# Arduino-Pro-v16_Silk_1.net
KiCad netlist of a schematic drawn in EAGLE
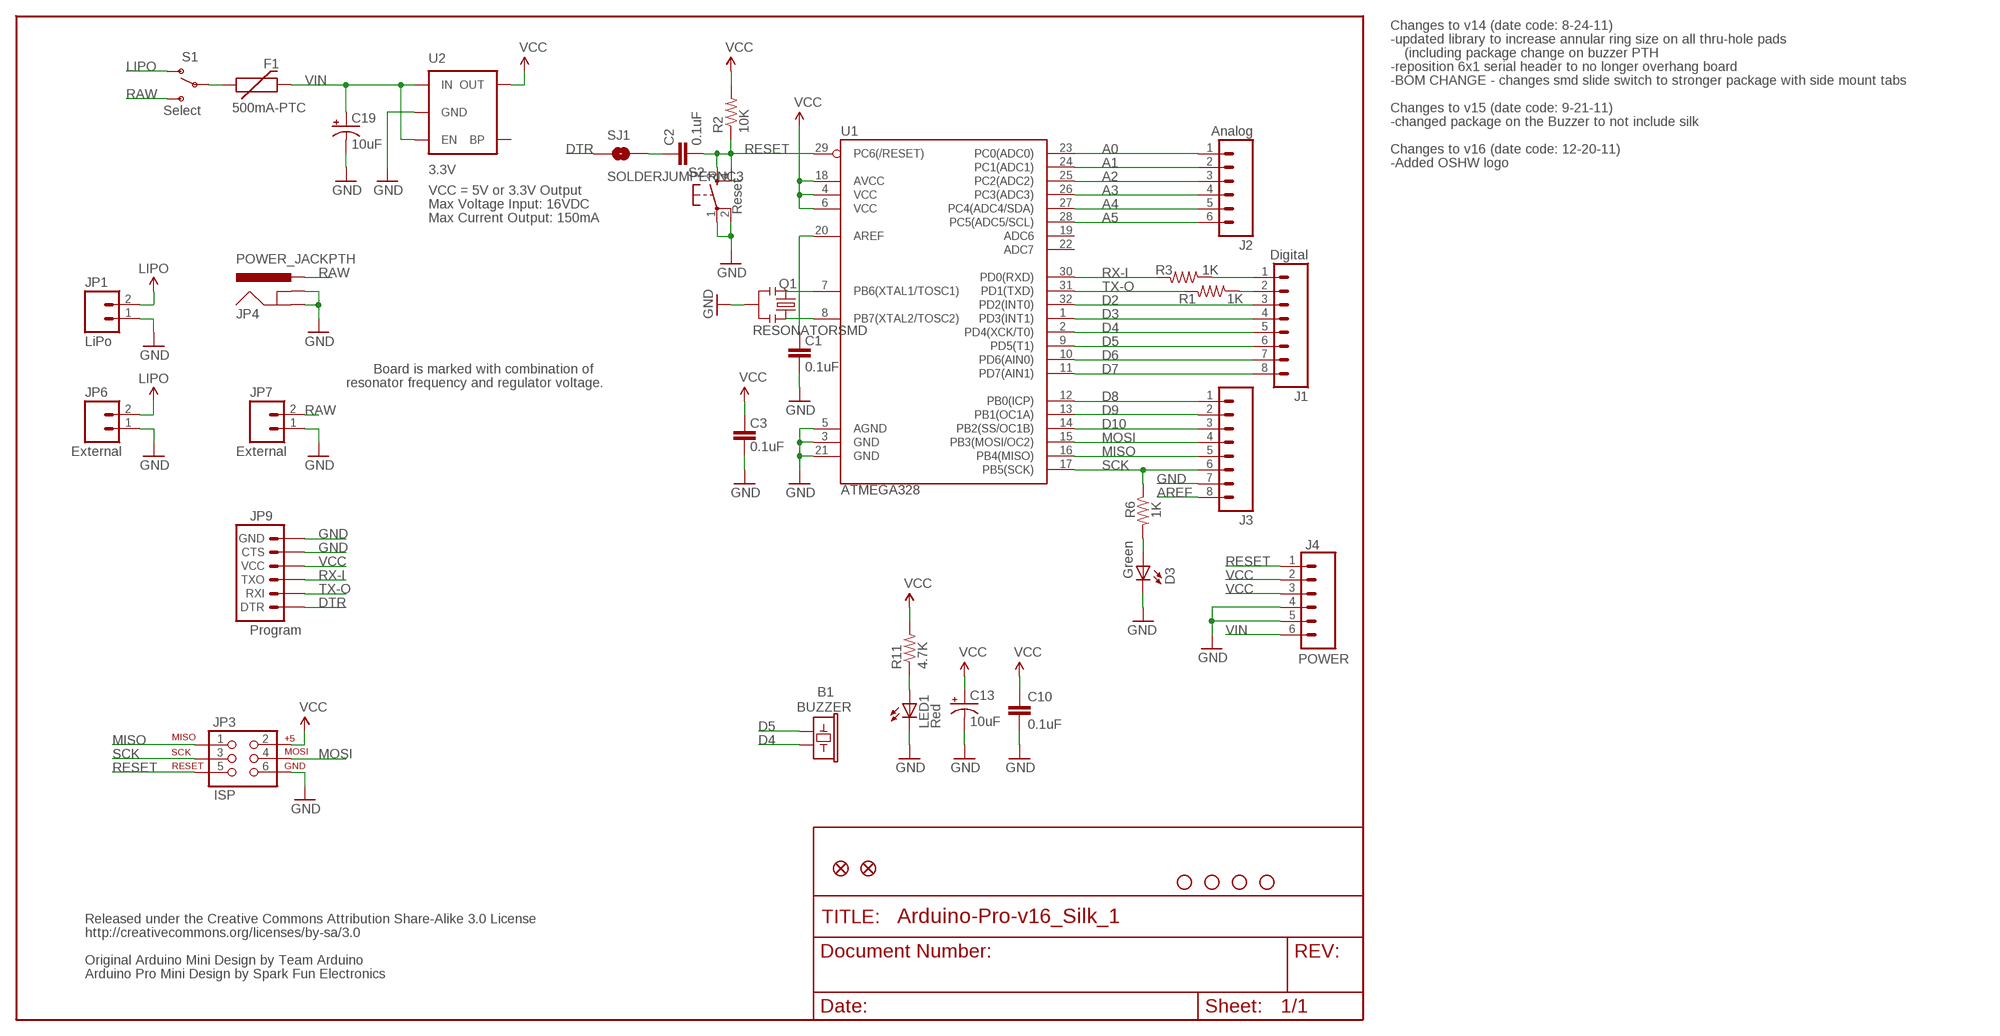
[diagram p0: schematic, sheet 1]

(export (version "E")
  (design (tool "Eeschema 10.0.6"))
  (components
    (comp (ref "B1")
      (value "BUZZER")
      (footprint "eagle-import:BUZZER-12MM-NS-KIT")
      (libsource (lib "eagle-import") (part "BUZZERPTH-NS-KIT"))
    )
    (comp (ref "C1")
      (value "0.1uF")
      (footprint "eagle-import:0402-CAP")
      (libsource (lib "eagle-import") (part "CAP0402-CAP"))
    )
    (comp (ref "C2")
      (value "0.1uF")
      (footprint "eagle-import:0402-CAP")
      (libsource (lib "eagle-import") (part "CAP0402-CAP"))
    )
    (comp (ref "C3")
      (value "0.1uF")
      (footprint "eagle-import:0402-CAP")
      (libsource (lib "eagle-import") (part "CAP0402-CAP"))
    )
    (comp (ref "C10")
      (value "0.1uF")
      (footprint "eagle-import:0402-CAP")
      (libsource (lib "eagle-import") (part "CAP0402-CAP"))
    )
    (comp (ref "C13")
      (value "10uF")
      (footprint "eagle-import:EIA3216")
      (libsource (lib "eagle-import") (part "CAP_POL1206"))
    )
    (comp (ref "C19")
      (value "10uF")
      (footprint "eagle-import:EIA3216")
      (libsource (lib "eagle-import") (part "CAP_POL1206"))
    )
    (comp (ref "D3")
      (value "Green")
      (footprint "eagle-import:LED-0603")
      (libsource (lib "eagle-import") (part "LED0603"))
    )
    (comp (ref "F1")
      (value "500mA-PTC")
      (footprint "eagle-import:PTC-1206")
      (libsource (lib "eagle-import") (part "PTCSMD"))
    )
    (comp (ref "J1")
      (value "Digital")
      (footprint "eagle-import:1X08")
      (libsource (lib "eagle-import") (part "M081X08"))
    )
    (comp (ref "J2")
      (value "Analog")
      (footprint "eagle-import:1X06")
      (libsource (lib "eagle-import") (part "M06SIP"))
    )
    (comp (ref "J3")
      (value "M081X08")
      (footprint "eagle-import:1X08")
      (libsource (lib "eagle-import") (part "M081X08"))
    )
    (comp (ref "J4")
      (value "POWER")
      (footprint "eagle-import:1X06")
      (libsource (lib "eagle-import") (part "M06SIP"))
    )
    (comp (ref "JP1")
      (value "LiPo")
      (footprint "eagle-import:JST-2-SMD")
      (libsource (lib "eagle-import") (part "M02-JST-2MM-SMT"))
    )
    (comp (ref "JP2")
      (value "FIDUCIAL1X2.5")
      (footprint "eagle-import:FIDUCIAL-1X2.5")
      (libsource (lib "eagle-import") (part "FIDUCIAL1X2.5"))
    )
    (comp (ref "JP3")
      (value "ISP")
      (footprint "eagle-import:2X3")
      (libsource (lib "eagle-import") (part "AVR_SPI_PRG_6PTH"))
    )
    (comp (ref "JP4")
      (value "POWER_JACKPTH")
      (footprint "eagle-import:POWER_JACK_PTH")
      (libsource (lib "eagle-import") (part "POWER_JACKPTH"))
    )
    (comp (ref "JP5")
      (value "FIDUCIAL1X2.5")
      (footprint "eagle-import:FIDUCIAL-1X2.5")
      (libsource (lib "eagle-import") (part "FIDUCIAL1X2.5"))
    )
    (comp (ref "JP6")
      (value "External")
      (footprint "eagle-import:1X02")
      (libsource (lib "eagle-import") (part "M02PTH"))
    )
    (comp (ref "JP7")
      (value "External")
      (footprint "eagle-import:1X02")
      (libsource (lib "eagle-import") (part "M02PTH"))
    )
    (comp (ref "JP9")
      (value "Program")
      (footprint "eagle-import:1X06-SMD")
      (libsource (lib "eagle-import") (part "ARDUINO_SERIAL_PROGRAMSMD"))
    )
    (comp (ref "LED1")
      (value "Red")
      (footprint "eagle-import:LED-0603")
      (libsource (lib "eagle-import") (part "LED0603"))
    )
    (comp (ref "Q1")
      (value "RESONATORSMD")
      (footprint "eagle-import:RESONATOR-SMD")
      (libsource (lib "eagle-import") (part "RESONATORSMD"))
    )
    (comp (ref "R1")
      (value "1K")
      (footprint "eagle-import:0402-RES")
      (libsource (lib "eagle-import") (part "RESISTOR0402-RES"))
    )
    (comp (ref "R2")
      (value "10K")
      (footprint "eagle-import:0402-RES")
      (libsource (lib "eagle-import") (part "RESISTOR0402-RES"))
    )
    (comp (ref "R3")
      (value "1K")
      (footprint "eagle-import:0402-RES")
      (libsource (lib "eagle-import") (part "RESISTOR0402-RES"))
    )
    (comp (ref "R6")
      (value "1K")
      (footprint "eagle-import:0402-RES")
      (libsource (lib "eagle-import") (part "RESISTOR0402-RES"))
    )
    (comp (ref "R11")
      (value "4.7K")
      (footprint "eagle-import:0402-RES")
      (libsource (lib "eagle-import") (part "RESISTOR0402-RES"))
    )
    (comp (ref "S1")
      (value "Select")
      (footprint "eagle-import:SWITCH-SPST-SMD-A")
      (libsource (lib "eagle-import") (part "SWITCH-SPST-SMD-A"))
    )
    (comp (ref "S2")
      (value "Reset")
      (footprint "eagle-import:TACTILE_SWITCH_SMD")
      (libsource (lib "eagle-import") (part "TAC_SWITCHSMD"))
    )
    (comp (ref "SJ1")
      (value "SOLDERJUMPERNC3")
      (footprint "eagle-import:SJ_2S-NOTRACE")
      (libsource (lib "eagle-import") (part "SOLDERJUMPERNC2"))
    )
    (comp (ref "U$1")
      (value "STAND-OFF")
      (footprint "eagle-import:STAND-OFF")
      (libsource (lib "eagle-import") (part "STAND-OFF"))
    )
    (comp (ref "U$3")
      (value "STAND-OFF")
      (footprint "eagle-import:STAND-OFF")
      (libsource (lib "eagle-import") (part "STAND-OFF"))
    )
    (comp (ref "U$9")
      (value "STAND-OFF")
      (footprint "eagle-import:STAND-OFF")
      (libsource (lib "eagle-import") (part "STAND-OFF"))
    )
    (comp (ref "U$10")
      (value "STAND-OFF")
      (footprint "eagle-import:STAND-OFF")
      (libsource (lib "eagle-import") (part "STAND-OFF"))
    )
    (comp (ref "U1")
      (value "ATMEGA328")
      (footprint "eagle-import:TQFP32-08")
      (libsource (lib "eagle-import") (part "ATMEGA168"))
    )
    (comp (ref "U2")
      (value "3.3V")
      (footprint "eagle-import:SOT23-5")
      (libsource (lib "eagle-import") (part "V_REG_LDOSMD"))
    )
  )
  (nets
    (net (code "1") (name "/A0") (class "Default")
      (node (ref "J2") (pin "1") (pinfunction "1_1") (pintype "passive"))
      (node (ref "U1") (pin "23") (pinfunction "PC0(ADC0)_23") (pintype "bidirectional"))
    )
    (net (code "2") (name "/A1") (class "Default")
      (node (ref "J2") (pin "2") (pinfunction "2_2") (pintype "passive"))
      (node (ref "U1") (pin "24") (pinfunction "PC1(ADC1)_24") (pintype "bidirectional"))
    )
    (net (code "3") (name "/A2") (class "Default")
      (node (ref "J2") (pin "3") (pinfunction "3_3") (pintype "passive"))
      (node (ref "U1") (pin "25") (pinfunction "PC2(ADC2)_25") (pintype "bidirectional"))
    )
    (net (code "4") (name "/A3") (class "Default")
      (node (ref "J2") (pin "4") (pinfunction "4_4") (pintype "passive"))
      (node (ref "U1") (pin "26") (pinfunction "PC3(ADC3)_26") (pintype "bidirectional"))
    )
    (net (code "5") (name "/A4") (class "Default")
      (node (ref "J2") (pin "5") (pinfunction "5_5") (pintype "passive"))
      (node (ref "U1") (pin "27") (pinfunction "PC4(ADC4/SDA)_27") (pintype "bidirectional"))
    )
    (net (code "6") (name "/A5") (class "Default")
      (node (ref "J2") (pin "6") (pinfunction "6_6") (pintype "passive"))
      (node (ref "U1") (pin "28") (pinfunction "PC5(ADC5/SCL)_28") (pintype "bidirectional"))
    )
    (net (code "7") (name "/AREF") (class "Default")
      (node (ref "C1") (pin "2") (pinfunction "2_2") (pintype "passive"))
      (node (ref "J3") (pin "8") (pinfunction "8_8") (pintype "passive"))
      (node (ref "U1") (pin "20") (pinfunction "AREF_20") (pintype "bidirectional"))
    )
    (net (code "8") (name "/D2") (class "Default")
      (node (ref "J1") (pin "3") (pinfunction "3_3") (pintype "passive"))
      (node (ref "U1") (pin "32") (pinfunction "PD2(INT0)_32") (pintype "bidirectional"))
    )
    (net (code "9") (name "/D3") (class "Default")
      (node (ref "J1") (pin "4") (pinfunction "4_4") (pintype "passive"))
      (node (ref "U1") (pin "1") (pinfunction "PD3(INT1)_1") (pintype "bidirectional"))
    )
    (net (code "10") (name "/D4") (class "Default")
      (node (ref "B1") (pin "-") (pinfunction "2_-") (pintype "passive"))
      (node (ref "J1") (pin "5") (pinfunction "5_5") (pintype "passive"))
      (node (ref "U1") (pin "2") (pinfunction "PD4(XCK/T0)_2") (pintype "bidirectional"))
    )
    (net (code "11") (name "/D5") (class "Default")
      (node (ref "B1") (pin "+") (pinfunction "1_+") (pintype "passive"))
      (node (ref "J1") (pin "6") (pinfunction "6_6") (pintype "passive"))
      (node (ref "U1") (pin "9") (pinfunction "PD5(T1)_9") (pintype "bidirectional"))
    )
    (net (code "12") (name "/D6") (class "Default")
      (node (ref "J1") (pin "7") (pinfunction "7_7") (pintype "passive"))
      (node (ref "U1") (pin "10") (pinfunction "PD6(AIN0)_10") (pintype "bidirectional"))
    )
    (net (code "13") (name "/D7") (class "Default")
      (node (ref "J1") (pin "8") (pinfunction "8_8") (pintype "passive"))
      (node (ref "U1") (pin "11") (pinfunction "PD7(AIN1)_11") (pintype "bidirectional"))
    )
    (net (code "14") (name "/D8") (class "Default")
      (node (ref "J3") (pin "1") (pinfunction "1_1") (pintype "passive"))
      (node (ref "U1") (pin "12") (pinfunction "PB0(ICP)_12") (pintype "bidirectional"))
    )
    (net (code "15") (name "/D9") (class "Default")
      (node (ref "J3") (pin "2") (pinfunction "2_2") (pintype "passive"))
      (node (ref "U1") (pin "13") (pinfunction "PB1(OC1A)_13") (pintype "bidirectional"))
    )
    (net (code "16") (name "/D10") (class "Default")
      (node (ref "J3") (pin "3") (pinfunction "3_3") (pintype "passive"))
      (node (ref "U1") (pin "14") (pinfunction "PB2(SS/OC1B)_14") (pintype "bidirectional"))
    )
    (net (code "17") (name "/DTR") (class "Default")
      (node (ref "JP9") (pin "1") (pinfunction "DTR_1") (pintype "passive"))
      (node (ref "SJ1") (pin "1") (pinfunction "1_1") (pintype "passive"))
    )
    (net (code "18") (name "/MISO") (class "Default")
      (node (ref "J3") (pin "5") (pinfunction "5_5") (pintype "passive"))
      (node (ref "JP3") (pin "1") (pinfunction "1_1") (pintype "passive"))
      (node (ref "U1") (pin "16") (pinfunction "PB4(MISO)_16") (pintype "bidirectional"))
    )
    (net (code "19") (name "/MOSI") (class "Default")
      (node (ref "J3") (pin "4") (pinfunction "4_4") (pintype "passive"))
      (node (ref "JP3") (pin "4") (pinfunction "4_4") (pintype "passive"))
      (node (ref "U1") (pin "15") (pinfunction "PB3(MOSI/OC2)_15") (pintype "bidirectional"))
    )
    (net (code "20") (name "/RAW") (class "Default")
      (node (ref "JP4") (pin "PWR") (pinfunction "PWR_PWR") (pintype "bidirectional"))
      (node (ref "JP7") (pin "2") (pinfunction "2_2") (pintype "passive"))
      (node (ref "S1") (pin "3") (pinfunction "S_3") (pintype "passive"))
    )
    (net (code "21") (name "/RESET") (class "Default")
      (node (ref "C2") (pin "2") (pinfunction "2_2") (pintype "passive"))
      (node (ref "J4") (pin "1") (pinfunction "1_1") (pintype "passive"))
      (node (ref "JP3") (pin "5") (pinfunction "5_5") (pintype "passive"))
      (node (ref "R2") (pin "1") (pinfunction "1_1") (pintype "passive"))
      (node (ref "S2") (pin "3") (pinfunction "3_3") (pintype "passive"))
      (node (ref "S2") (pin "4") (pinfunction "4_4") (pintype "passive"))
      (node (ref "U1") (pin "29") (pinfunction "PC6(/RESET)_29") (pintype "bidirectional"))
    )
    (net (code "22") (name "/RX-I") (class "Default")
      (node (ref "JP9") (pin "3") (pinfunction "TXO_3") (pintype "passive"))
      (node (ref "R3") (pin "2") (pinfunction "2_2") (pintype "passive"))
      (node (ref "U1") (pin "30") (pinfunction "PD0(RXD)_30") (pintype "bidirectional"))
    )
    (net (code "23") (name "/SCK") (class "Default")
      (node (ref "J3") (pin "6") (pinfunction "6_6") (pintype "passive"))
      (node (ref "JP3") (pin "3") (pinfunction "3_3") (pintype "passive"))
      (node (ref "R6") (pin "1") (pinfunction "1_1") (pintype "passive"))
      (node (ref "U1") (pin "17") (pinfunction "PB5(SCK)_17") (pintype "bidirectional"))
    )
    (net (code "24") (name "/TX-O") (class "Default")
      (node (ref "JP9") (pin "2") (pinfunction "RXI_2") (pintype "passive"))
      (node (ref "R1") (pin "2") (pinfunction "2_2") (pintype "passive"))
      (node (ref "U1") (pin "31") (pinfunction "PD1(TXD)_31") (pintype "bidirectional"))
    )
    (net (code "25") (name "/VIN") (class "Default")
      (node (ref "C19") (pin "A") (pinfunction "+_A") (pintype "passive"))
      (node (ref "F1") (pin "2") (pinfunction "2_2") (pintype "bidirectional"))
      (node (ref "J4") (pin "6") (pinfunction "6_6") (pintype "passive"))
      (node (ref "U2") (pin "1") (pinfunction "IN_1") (pintype "input"))
      (node (ref "U2") (pin "3") (pinfunction "EN_3") (pintype "input"))
    )
    (net (code "26") (name "GND") (class "Default")
      (node (ref "C1") (pin "1") (pinfunction "1_1") (pintype "passive"))
      (node (ref "C10") (pin "2") (pinfunction "2_2") (pintype "passive"))
      (node (ref "C13") (pin "C") (pinfunction "-_C") (pintype "passive"))
      (node (ref "C19") (pin "C") (pinfunction "-_C") (pintype "passive"))
      (node (ref "C3") (pin "1") (pinfunction "1_1") (pintype "passive"))
      (node (ref "D3") (pin "C") (pinfunction "C_C") (pintype "passive"))
      (node (ref "J3") (pin "7") (pinfunction "7_7") (pintype "passive"))
      (node (ref "J4") (pin "4") (pinfunction "4_4") (pintype "passive"))
      (node (ref "J4") (pin "5") (pinfunction "5_5") (pintype "passive"))
      (node (ref "JP1") (pin "1") (pinfunction "1_1") (pintype "passive"))
      (node (ref "JP3") (pin "6") (pinfunction "6_6") (pintype "passive"))
      (node (ref "JP4") (pin "GND") (pinfunction "GND_GND") (pintype "bidirectional"))
      (node (ref "JP4") (pin "GNDBREAK") (pinfunction "GNDBREAK_GNDBREAK") (pintype "bidirectional"))
      (node (ref "JP6") (pin "1") (pinfunction "1_1") (pintype "passive"))
      (node (ref "JP7") (pin "1") (pinfunction "1_1") (pintype "passive"))
      (node (ref "JP9") (pin "5") (pinfunction "CTS_5") (pintype "passive"))
      (node (ref "JP9") (pin "6") (pinfunction "GND_6") (pintype "passive"))
      (node (ref "LED1") (pin "C") (pinfunction "C_C") (pintype "passive"))
      (node (ref "Q1") (pin "2") (pinfunction "2_2") (pintype "passive"))
      (node (ref "S2") (pin "1") (pinfunction "1_1") (pintype "passive"))
      (node (ref "S2") (pin "2") (pinfunction "2_2") (pintype "passive"))
      (node (ref "U1") (pin "21") (pinfunction "GND_21") (pintype "bidirectional"))
      (node (ref "U1") (pin "3") (pinfunction "GND_3") (pintype "bidirectional"))
      (node (ref "U1") (pin "5") (pinfunction "AGND_5") (pintype "bidirectional"))
      (node (ref "U2") (pin "2") (pinfunction "GND_2") (pintype "input"))
    )
    (net (code "27") (name "LIPO") (class "Default")
      (node (ref "JP1") (pin "2") (pinfunction "2_2") (pintype "passive"))
      (node (ref "JP6") (pin "2") (pinfunction "2_2") (pintype "passive"))
      (node (ref "S1") (pin "1") (pinfunction "O_1") (pintype "passive"))
    )
    (net (code "28") (name "Net-(C2-Pad1)") (class "Default")
      (node (ref "C2") (pin "1") (pinfunction "1_1") (pintype "passive"))
      (node (ref "SJ1") (pin "2") (pinfunction "2_2") (pintype "passive"))
    )
    (net (code "29") (name "Net-(D3-PadA)") (class "Default")
      (node (ref "D3") (pin "A") (pinfunction "A_A") (pintype "passive"))
      (node (ref "R6") (pin "2") (pinfunction "2_2") (pintype "passive"))
    )
    (net (code "30") (name "Net-(J1-Pad1)") (class "Default")
      (node (ref "J1") (pin "1") (pinfunction "1_1") (pintype "passive"))
      (node (ref "R3") (pin "1") (pinfunction "1_1") (pintype "passive"))
    )
    (net (code "31") (name "Net-(J1-Pad2)") (class "Default")
      (node (ref "J1") (pin "2") (pinfunction "2_2") (pintype "passive"))
      (node (ref "R1") (pin "1") (pinfunction "1_1") (pintype "passive"))
    )
    (net (code "32") (name "Net-(LED1-PadA)") (class "Default")
      (node (ref "LED1") (pin "A") (pinfunction "A_A") (pintype "passive"))
      (node (ref "R11") (pin "1") (pinfunction "1_1") (pintype "passive"))
    )
    (net (code "33") (name "Net-(S1-P)") (class "Default")
      (node (ref "F1") (pin "1") (pinfunction "1_1") (pintype "bidirectional"))
      (node (ref "S1") (pin "2") (pinfunction "P_2") (pintype "passive"))
    )
    (net (code "34") (name "Net-(U1-PB6(XTAL1{slash}TOSC1))") (class "Default")
      (node (ref "Q1") (pin "3") (pinfunction "3_3") (pintype "passive"))
      (node (ref "U1") (pin "7") (pinfunction "PB6(XTAL1/TOSC1)_7") (pintype "bidirectional"))
    )
    (net (code "35") (name "Net-(U1-PB7(XTAL2{slash}TOSC2))") (class "Default")
      (node (ref "Q1") (pin "1") (pinfunction "1_1") (pintype "passive"))
      (node (ref "U1") (pin "8") (pinfunction "PB7(XTAL2/TOSC2)_8") (pintype "bidirectional"))
    )
    (net (code "36") (name "VCC") (class "Default")
      (node (ref "C10") (pin "1") (pinfunction "1_1") (pintype "passive"))
      (node (ref "C13") (pin "A") (pinfunction "+_A") (pintype "passive"))
      (node (ref "C3") (pin "2") (pinfunction "2_2") (pintype "passive"))
      (node (ref "J4") (pin "2") (pinfunction "2_2") (pintype "passive"))
      (node (ref "J4") (pin "3") (pinfunction "3_3") (pintype "passive"))
      (node (ref "JP3") (pin "2") (pinfunction "2_2") (pintype "passive"))
      (node (ref "JP9") (pin "4") (pinfunction "VCC_4") (pintype "passive"))
      (node (ref "R11") (pin "2") (pinfunction "2_2") (pintype "passive"))
      (node (ref "R2") (pin "2") (pinfunction "2_2") (pintype "passive"))
      (node (ref "U1") (pin "18") (pinfunction "AVCC_18") (pintype "bidirectional"))
      (node (ref "U1") (pin "4") (pinfunction "VCC_4") (pintype "bidirectional"))
      (node (ref "U1") (pin "6") (pinfunction "VCC_6") (pintype "bidirectional"))
      (node (ref "U2") (pin "5") (pinfunction "OUT_5") (pintype "passive"))
    )
    (net (code "37") (name "unconnected-(U1-ADC6-Pad19)") (class "Default")
      (node (ref "U1") (pin "19") (pinfunction "ADC6_19") (pintype "bidirectional"))
    )
    (net (code "38") (name "unconnected-(U1-ADC7-Pad22)") (class "Default")
      (node (ref "U1") (pin "22") (pinfunction "ADC7_22") (pintype "bidirectional"))
    )
    (net (code "39") (name "unconnected-(U2-BP-Pad4)") (class "Default")
      (node (ref "U2") (pin "4") (pinfunction "BP_4") (pintype "input"))
    )
  )
)
